# Beagle_ESC.net
KiCad netlist of a schematic drawn in EAGLE
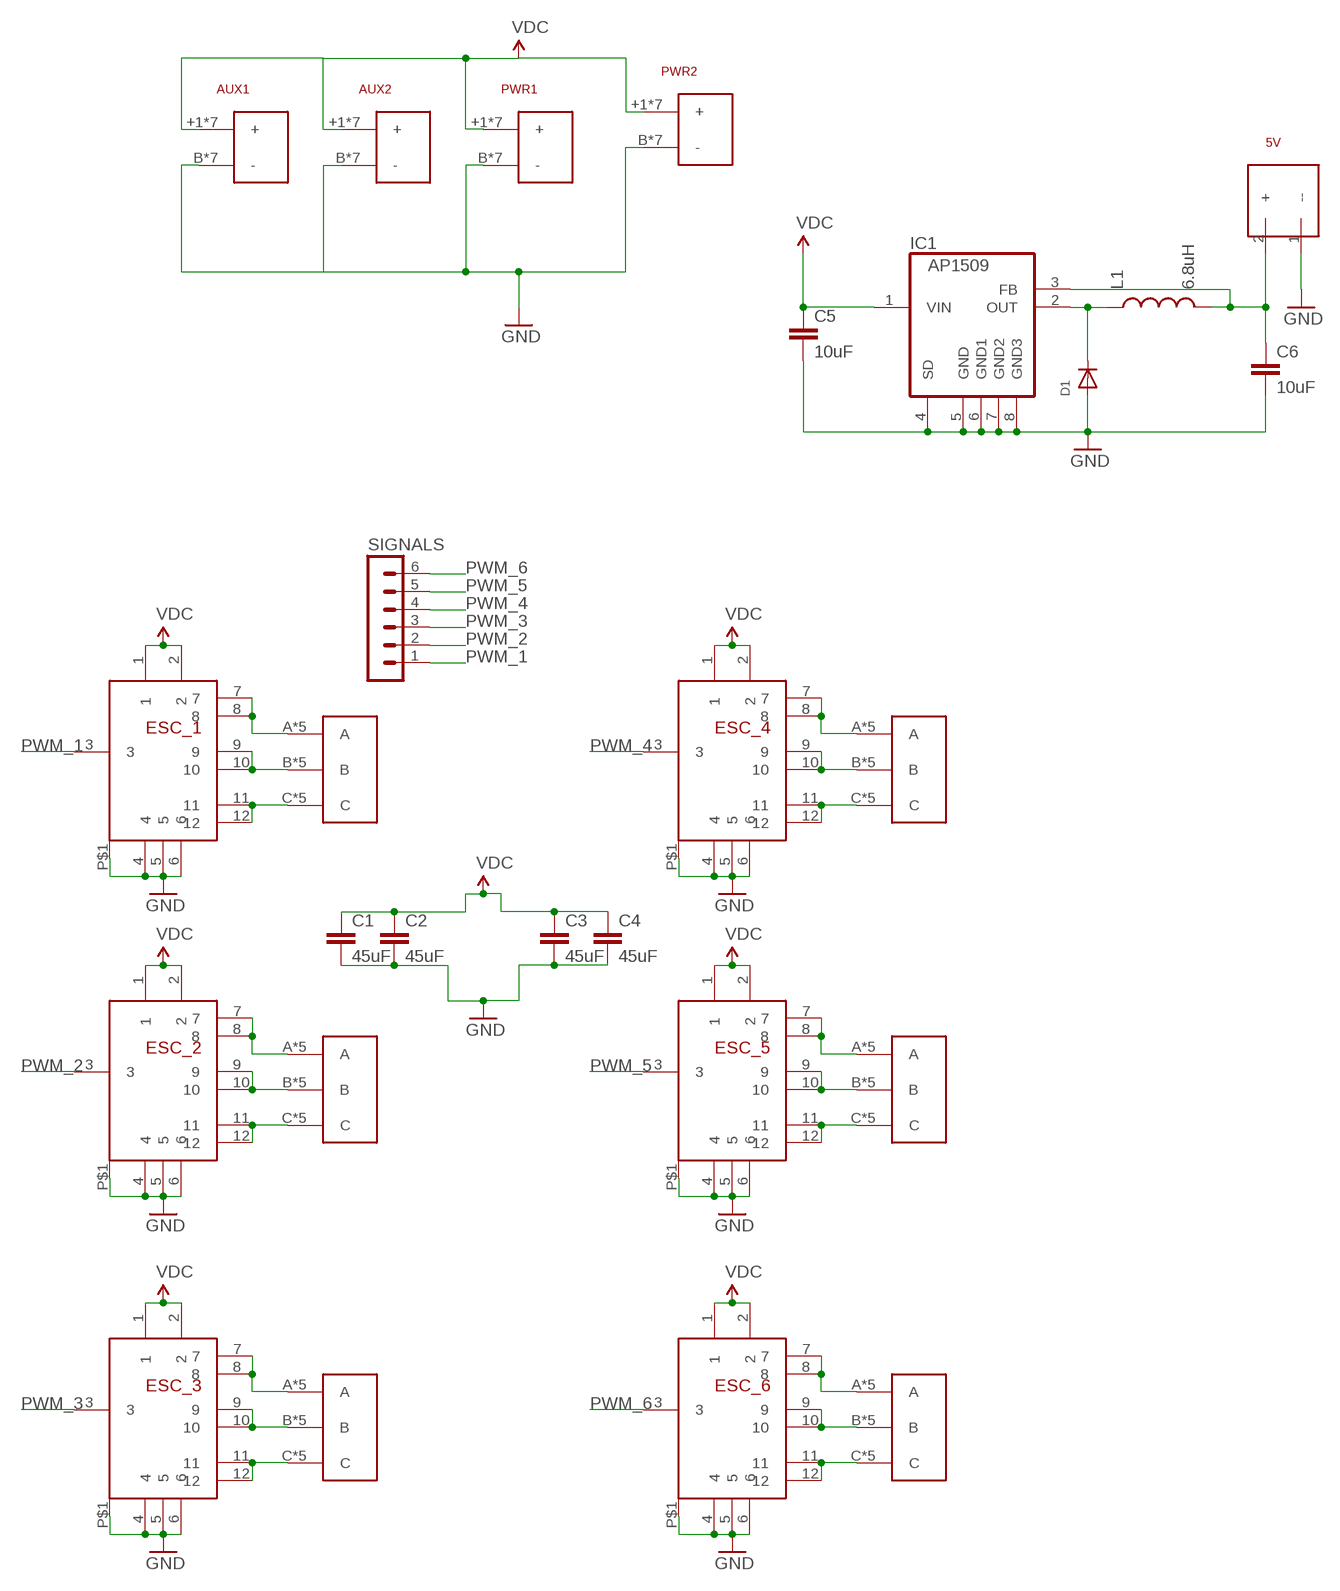
[diagram p0: schematic, sheet 1]

(export (version "E")
  (design (tool "Eeschema 10.0.6"))
  (components
    (comp (ref "1")
      (value "3_PADS")
      (footprint "eagle-import:3_PADS")
      (libsource (lib "eagle-import") (part "3_PADS"))
    )
    (comp (ref "2")
      (value "3_PADS")
      (footprint "eagle-import:3_PADS")
      (libsource (lib "eagle-import") (part "3_PADS"))
    )
    (comp (ref "3")
      (value "3_PADS")
      (footprint "eagle-import:3_PADS")
      (libsource (lib "eagle-import") (part "3_PADS"))
    )
    (comp (ref "4")
      (value "3_PADS")
      (footprint "eagle-import:3_PADS")
      (libsource (lib "eagle-import") (part "3_PADS"))
    )
    (comp (ref "5")
      (value "3_PADS")
      (footprint "eagle-import:3_PADS")
      (libsource (lib "eagle-import") (part "3_PADS"))
    )
    (comp (ref "5V")
      (value "HEADER_PWR")
      (footprint "eagle-import:HEADER_PWR")
      (libsource (lib "eagle-import") (part "HEADER_PWR"))
    )
    (comp (ref "6")
      (value "3_PADS")
      (footprint "eagle-import:3_PADS")
      (libsource (lib "eagle-import") (part "3_PADS"))
    )
    (comp (ref "AUX1")
      (value "2PADS")
      (footprint "eagle-import:2PADS")
      (libsource (lib "eagle-import") (part "2PADS"))
    )
    (comp (ref "AUX2")
      (value "2PADS")
      (footprint "eagle-import:2PADS")
      (libsource (lib "eagle-import") (part "2PADS"))
    )
    (comp (ref "C1")
      (value "45uF")
      (footprint "eagle-import:1206")
      (libsource (lib "eagle-import") (part "CAP1206"))
    )
    (comp (ref "C2")
      (value "45uF")
      (footprint "eagle-import:1206")
      (libsource (lib "eagle-import") (part "CAP1206"))
    )
    (comp (ref "C3")
      (value "45uF")
      (footprint "eagle-import:1206")
      (libsource (lib "eagle-import") (part "CAP1206"))
    )
    (comp (ref "C4")
      (value "45uF")
      (footprint "eagle-import:1206")
      (libsource (lib "eagle-import") (part "CAP1206"))
    )
    (comp (ref "C5")
      (value "10uF")
      (footprint "eagle-import:0805")
      (libsource (lib "eagle-import") (part "CAP0805"))
    )
    (comp (ref "C6")
      (value "10uF")
      (footprint "eagle-import:0805")
      (libsource (lib "eagle-import") (part "CAP0805"))
    )
    (comp (ref "D1")
      (value "DIODESOD-123")
      (footprint "eagle-import:SOD-123")
      (libsource (lib "eagle-import") (part "DIODESOD-123"))
    )
    (comp (ref "ESC_1")
      (value "DYS_BLHELI_ESC")
      (footprint "eagle-import:DYS_BLHELI_ESC")
      (libsource (lib "eagle-import") (part "DYS_BLHELI_ESC"))
    )
    (comp (ref "ESC_2")
      (value "DYS_BLHELI_ESC")
      (footprint "eagle-import:DYS_BLHELI_ESC")
      (libsource (lib "eagle-import") (part "DYS_BLHELI_ESC"))
    )
    (comp (ref "ESC_3")
      (value "DYS_BLHELI_ESC")
      (footprint "eagle-import:DYS_BLHELI_ESC")
      (libsource (lib "eagle-import") (part "DYS_BLHELI_ESC"))
    )
    (comp (ref "ESC_4")
      (value "DYS_BLHELI_ESC")
      (footprint "eagle-import:DYS_BLHELI_ESC")
      (libsource (lib "eagle-import") (part "DYS_BLHELI_ESC"))
    )
    (comp (ref "ESC_5")
      (value "DYS_BLHELI_ESC")
      (footprint "eagle-import:DYS_BLHELI_ESC")
      (libsource (lib "eagle-import") (part "DYS_BLHELI_ESC"))
    )
    (comp (ref "ESC_6")
      (value "DYS_BLHELI_ESC")
      (footprint "eagle-import:DYS_BLHELI_ESC")
      (libsource (lib "eagle-import") (part "DYS_BLHELI_ESC"))
    )
    (comp (ref "IC1")
      (value "AP1509SOIC-8-TIGHT")
      (footprint "eagle-import:SO08-TIGHT")
      (libsource (lib "eagle-import") (part "AP1509SOIC-8-TIGHT"))
    )
    (comp (ref "L1")
      (value "6.8uH")
      (footprint "eagle-import:TAIYO_NRS")
      (libsource (lib "eagle-import") (part "INDUCTORTAIYO_NR-S"))
    )
    (comp (ref "PWR1")
      (value "2PADS")
      (footprint "eagle-import:2PADS")
      (libsource (lib "eagle-import") (part "2PADS"))
    )
    (comp (ref "PWR2")
      (value "2PADS")
      (footprint "eagle-import:2PADS")
      (libsource (lib "eagle-import") (part "2PADS"))
    )
    (comp (ref "SIGNALS")
      (value "MA06-1")
      (footprint "eagle-import:MA06-1")
      (libsource (lib "eagle-import") (part "MA06-1"))
    )
  )
  (nets
    (net (code "1") (name "/PWM_1") (class "Default")
      (node (ref "ESC_1") (pin "3") (pinfunction "3_3") (pintype "input"))
      (node (ref "SIGNALS") (pin "1") (pinfunction "1_1") (pintype "passive"))
    )
    (net (code "2") (name "/PWM_2") (class "Default")
      (node (ref "ESC_2") (pin "3") (pinfunction "3_3") (pintype "input"))
      (node (ref "SIGNALS") (pin "2") (pinfunction "2_2") (pintype "passive"))
    )
    (net (code "3") (name "/PWM_3") (class "Default")
      (node (ref "ESC_3") (pin "3") (pinfunction "3_3") (pintype "input"))
      (node (ref "SIGNALS") (pin "3") (pinfunction "3_3") (pintype "passive"))
    )
    (net (code "4") (name "/PWM_4") (class "Default")
      (node (ref "ESC_4") (pin "3") (pinfunction "3_3") (pintype "input"))
      (node (ref "SIGNALS") (pin "4") (pinfunction "4_4") (pintype "passive"))
    )
    (net (code "5") (name "/PWM_5") (class "Default")
      (node (ref "ESC_5") (pin "3") (pinfunction "3_3") (pintype "input"))
      (node (ref "SIGNALS") (pin "5") (pinfunction "5_5") (pintype "passive"))
    )
    (net (code "6") (name "/PWM_6") (class "Default")
      (node (ref "ESC_6") (pin "3") (pinfunction "3_3") (pintype "input"))
      (node (ref "SIGNALS") (pin "6") (pinfunction "6_6") (pintype "passive"))
    )
    (net (code "7") (name "GND") (class "Default")
      (node (ref "5V") (pin "1") (pinfunction "--_1") (pintype "bidirectional"))
      (node (ref "AUX1") (pin "B") (pinfunction "-_B") (pintype "bidirectional"))
      (node (ref "AUX1") (pin "P$10") (pinfunction "-_P$10") (pintype "bidirectional"))
      (node (ref "AUX1") (pin "P$11") (pinfunction "-_P$11") (pintype "bidirectional"))
      (node (ref "AUX1") (pin "P$12") (pinfunction "-_P$12") (pintype "bidirectional"))
      (node (ref "AUX1") (pin "P$13") (pinfunction "-_P$13") (pintype "bidirectional"))
      (node (ref "AUX1") (pin "P$14") (pinfunction "-_P$14") (pintype "bidirectional"))
      (node (ref "AUX1") (pin "P$5") (pinfunction "-_P$5") (pintype "bidirectional"))
      (node (ref "AUX2") (pin "B") (pinfunction "-_B") (pintype "bidirectional"))
      (node (ref "AUX2") (pin "P$10") (pinfunction "-_P$10") (pintype "bidirectional"))
      (node (ref "AUX2") (pin "P$11") (pinfunction "-_P$11") (pintype "bidirectional"))
      (node (ref "AUX2") (pin "P$12") (pinfunction "-_P$12") (pintype "bidirectional"))
      (node (ref "AUX2") (pin "P$13") (pinfunction "-_P$13") (pintype "bidirectional"))
      (node (ref "AUX2") (pin "P$14") (pinfunction "-_P$14") (pintype "bidirectional"))
      (node (ref "AUX2") (pin "P$5") (pinfunction "-_P$5") (pintype "bidirectional"))
      (node (ref "C1") (pin "2") (pinfunction "2_2") (pintype "passive"))
      (node (ref "C2") (pin "2") (pinfunction "2_2") (pintype "passive"))
      (node (ref "C3") (pin "2") (pinfunction "2_2") (pintype "passive"))
      (node (ref "C4") (pin "2") (pinfunction "2_2") (pintype "passive"))
      (node (ref "C5") (pin "2") (pinfunction "2_2") (pintype "passive"))
      (node (ref "C6") (pin "2") (pinfunction "2_2") (pintype "passive"))
      (node (ref "D1") (pin "A") (pinfunction "A_A") (pintype "passive"))
      (node (ref "ESC_1") (pin "4") (pinfunction "4_4") (pintype "power_in"))
      (node (ref "ESC_1") (pin "5") (pinfunction "5_5") (pintype "power_in"))
      (node (ref "ESC_1") (pin "6") (pinfunction "6_6") (pintype "power_in"))
      (node (ref "ESC_1") (pin "P$1") (pinfunction "P$1_P$1") (pintype "power_in"))
      (node (ref "ESC_2") (pin "4") (pinfunction "4_4") (pintype "power_in"))
      (node (ref "ESC_2") (pin "5") (pinfunction "5_5") (pintype "power_in"))
      (node (ref "ESC_2") (pin "6") (pinfunction "6_6") (pintype "power_in"))
      (node (ref "ESC_2") (pin "P$1") (pinfunction "P$1_P$1") (pintype "power_in"))
      (node (ref "ESC_3") (pin "4") (pinfunction "4_4") (pintype "power_in"))
      (node (ref "ESC_3") (pin "5") (pinfunction "5_5") (pintype "power_in"))
      (node (ref "ESC_3") (pin "6") (pinfunction "6_6") (pintype "power_in"))
      (node (ref "ESC_3") (pin "P$1") (pinfunction "P$1_P$1") (pintype "power_in"))
      (node (ref "ESC_4") (pin "4") (pinfunction "4_4") (pintype "power_in"))
      (node (ref "ESC_4") (pin "5") (pinfunction "5_5") (pintype "power_in"))
      (node (ref "ESC_4") (pin "6") (pinfunction "6_6") (pintype "power_in"))
      (node (ref "ESC_4") (pin "P$1") (pinfunction "P$1_P$1") (pintype "power_in"))
      (node (ref "ESC_5") (pin "4") (pinfunction "4_4") (pintype "power_in"))
      (node (ref "ESC_5") (pin "5") (pinfunction "5_5") (pintype "power_in"))
      (node (ref "ESC_5") (pin "6") (pinfunction "6_6") (pintype "power_in"))
      (node (ref "ESC_5") (pin "P$1") (pinfunction "P$1_P$1") (pintype "power_in"))
      (node (ref "ESC_6") (pin "4") (pinfunction "4_4") (pintype "power_in"))
      (node (ref "ESC_6") (pin "5") (pinfunction "5_5") (pintype "power_in"))
      (node (ref "ESC_6") (pin "6") (pinfunction "6_6") (pintype "power_in"))
      (node (ref "ESC_6") (pin "P$1") (pinfunction "P$1_P$1") (pintype "power_in"))
      (node (ref "IC1") (pin "4") (pinfunction "SD_4") (pintype "input"))
      (node (ref "IC1") (pin "5") (pinfunction "GND_5") (pintype "power_in"))
      (node (ref "IC1") (pin "6") (pinfunction "GND1_6") (pintype "input"))
      (node (ref "IC1") (pin "7") (pinfunction "GND2_7") (pintype "passive"))
      (node (ref "IC1") (pin "8") (pinfunction "GND3_8") (pintype "power_in"))
      (node (ref "PWR1") (pin "B") (pinfunction "-_B") (pintype "bidirectional"))
      (node (ref "PWR1") (pin "P$10") (pinfunction "-_P$10") (pintype "bidirectional"))
      (node (ref "PWR1") (pin "P$11") (pinfunction "-_P$11") (pintype "bidirectional"))
      (node (ref "PWR1") (pin "P$12") (pinfunction "-_P$12") (pintype "bidirectional"))
      (node (ref "PWR1") (pin "P$13") (pinfunction "-_P$13") (pintype "bidirectional"))
      (node (ref "PWR1") (pin "P$14") (pinfunction "-_P$14") (pintype "bidirectional"))
      (node (ref "PWR1") (pin "P$5") (pinfunction "-_P$5") (pintype "bidirectional"))
      (node (ref "PWR2") (pin "B") (pinfunction "-_B") (pintype "bidirectional"))
      (node (ref "PWR2") (pin "P$10") (pinfunction "-_P$10") (pintype "bidirectional"))
      (node (ref "PWR2") (pin "P$11") (pinfunction "-_P$11") (pintype "bidirectional"))
      (node (ref "PWR2") (pin "P$12") (pinfunction "-_P$12") (pintype "bidirectional"))
      (node (ref "PWR2") (pin "P$13") (pinfunction "-_P$13") (pintype "bidirectional"))
      (node (ref "PWR2") (pin "P$14") (pinfunction "-_P$14") (pintype "bidirectional"))
      (node (ref "PWR2") (pin "P$5") (pinfunction "-_P$5") (pintype "bidirectional"))
    )
    (net (code "8") (name "Net-(1-A-PadP$4)") (class "Default")
      (node (ref "1") (pin "A") (pinfunction "A_A") (pintype "bidirectional"))
      (node (ref "1") (pin "P$4") (pinfunction "A_P$4") (pintype "bidirectional"))
      (node (ref "1") (pin "P$7") (pinfunction "A_P$7") (pintype "bidirectional"))
      (node (ref "1") (pin "P$8") (pinfunction "A_P$8") (pintype "bidirectional"))
      (node (ref "1") (pin "P$9") (pinfunction "A_P$9") (pintype "bidirectional"))
      (node (ref "ESC_1") (pin "7") (pinfunction "7_7") (pintype "output"))
      (node (ref "ESC_1") (pin "8") (pinfunction "8_8") (pintype "output"))
    )
    (net (code "9") (name "Net-(1-B-PadP$10)") (class "Default")
      (node (ref "1") (pin "B") (pinfunction "B_B") (pintype "bidirectional"))
      (node (ref "1") (pin "P$10") (pinfunction "B_P$10") (pintype "bidirectional"))
      (node (ref "1") (pin "P$11") (pinfunction "B_P$11") (pintype "bidirectional"))
      (node (ref "1") (pin "P$12") (pinfunction "B_P$12") (pintype "bidirectional"))
      (node (ref "1") (pin "P$5") (pinfunction "B_P$5") (pintype "bidirectional"))
      (node (ref "ESC_1") (pin "10") (pinfunction "10_10") (pintype "output"))
      (node (ref "ESC_1") (pin "9") (pinfunction "9_9") (pintype "output"))
    )
    (net (code "10") (name "Net-(1-C-PadP$13)") (class "Default")
      (node (ref "1") (pin "C") (pinfunction "C_C") (pintype "bidirectional"))
      (node (ref "1") (pin "P$13") (pinfunction "C_P$13") (pintype "bidirectional"))
      (node (ref "1") (pin "P$14") (pinfunction "C_P$14") (pintype "bidirectional"))
      (node (ref "1") (pin "P$15") (pinfunction "C_P$15") (pintype "bidirectional"))
      (node (ref "1") (pin "P$6") (pinfunction "C_P$6") (pintype "bidirectional"))
      (node (ref "ESC_1") (pin "11") (pinfunction "11_11") (pintype "output"))
      (node (ref "ESC_1") (pin "12") (pinfunction "12_12") (pintype "output"))
    )
    (net (code "11") (name "Net-(2-A-PadP$4)") (class "Default")
      (node (ref "2") (pin "A") (pinfunction "A_A") (pintype "bidirectional"))
      (node (ref "2") (pin "P$4") (pinfunction "A_P$4") (pintype "bidirectional"))
      (node (ref "2") (pin "P$7") (pinfunction "A_P$7") (pintype "bidirectional"))
      (node (ref "2") (pin "P$8") (pinfunction "A_P$8") (pintype "bidirectional"))
      (node (ref "2") (pin "P$9") (pinfunction "A_P$9") (pintype "bidirectional"))
      (node (ref "ESC_2") (pin "7") (pinfunction "7_7") (pintype "output"))
      (node (ref "ESC_2") (pin "8") (pinfunction "8_8") (pintype "output"))
    )
    (net (code "12") (name "Net-(2-B-PadP$10)") (class "Default")
      (node (ref "2") (pin "B") (pinfunction "B_B") (pintype "bidirectional"))
      (node (ref "2") (pin "P$10") (pinfunction "B_P$10") (pintype "bidirectional"))
      (node (ref "2") (pin "P$11") (pinfunction "B_P$11") (pintype "bidirectional"))
      (node (ref "2") (pin "P$12") (pinfunction "B_P$12") (pintype "bidirectional"))
      (node (ref "2") (pin "P$5") (pinfunction "B_P$5") (pintype "bidirectional"))
      (node (ref "ESC_2") (pin "10") (pinfunction "10_10") (pintype "output"))
      (node (ref "ESC_2") (pin "9") (pinfunction "9_9") (pintype "output"))
    )
    (net (code "13") (name "Net-(2-C-PadP$13)") (class "Default")
      (node (ref "2") (pin "C") (pinfunction "C_C") (pintype "bidirectional"))
      (node (ref "2") (pin "P$13") (pinfunction "C_P$13") (pintype "bidirectional"))
      (node (ref "2") (pin "P$14") (pinfunction "C_P$14") (pintype "bidirectional"))
      (node (ref "2") (pin "P$15") (pinfunction "C_P$15") (pintype "bidirectional"))
      (node (ref "2") (pin "P$6") (pinfunction "C_P$6") (pintype "bidirectional"))
      (node (ref "ESC_2") (pin "11") (pinfunction "11_11") (pintype "output"))
      (node (ref "ESC_2") (pin "12") (pinfunction "12_12") (pintype "output"))
    )
    (net (code "14") (name "Net-(3-A-PadP$4)") (class "Default")
      (node (ref "3") (pin "A") (pinfunction "A_A") (pintype "bidirectional"))
      (node (ref "3") (pin "P$4") (pinfunction "A_P$4") (pintype "bidirectional"))
      (node (ref "3") (pin "P$7") (pinfunction "A_P$7") (pintype "bidirectional"))
      (node (ref "3") (pin "P$8") (pinfunction "A_P$8") (pintype "bidirectional"))
      (node (ref "3") (pin "P$9") (pinfunction "A_P$9") (pintype "bidirectional"))
      (node (ref "ESC_3") (pin "7") (pinfunction "7_7") (pintype "output"))
      (node (ref "ESC_3") (pin "8") (pinfunction "8_8") (pintype "output"))
    )
    (net (code "15") (name "Net-(3-B-PadP$10)") (class "Default")
      (node (ref "3") (pin "B") (pinfunction "B_B") (pintype "bidirectional"))
      (node (ref "3") (pin "P$10") (pinfunction "B_P$10") (pintype "bidirectional"))
      (node (ref "3") (pin "P$11") (pinfunction "B_P$11") (pintype "bidirectional"))
      (node (ref "3") (pin "P$12") (pinfunction "B_P$12") (pintype "bidirectional"))
      (node (ref "3") (pin "P$5") (pinfunction "B_P$5") (pintype "bidirectional"))
      (node (ref "ESC_3") (pin "10") (pinfunction "10_10") (pintype "output"))
      (node (ref "ESC_3") (pin "9") (pinfunction "9_9") (pintype "output"))
    )
    (net (code "16") (name "Net-(3-C-PadP$13)") (class "Default")
      (node (ref "3") (pin "C") (pinfunction "C_C") (pintype "bidirectional"))
      (node (ref "3") (pin "P$13") (pinfunction "C_P$13") (pintype "bidirectional"))
      (node (ref "3") (pin "P$14") (pinfunction "C_P$14") (pintype "bidirectional"))
      (node (ref "3") (pin "P$15") (pinfunction "C_P$15") (pintype "bidirectional"))
      (node (ref "3") (pin "P$6") (pinfunction "C_P$6") (pintype "bidirectional"))
      (node (ref "ESC_3") (pin "11") (pinfunction "11_11") (pintype "output"))
      (node (ref "ESC_3") (pin "12") (pinfunction "12_12") (pintype "output"))
    )
    (net (code "17") (name "Net-(4-A-PadP$4)") (class "Default")
      (node (ref "4") (pin "A") (pinfunction "A_A") (pintype "bidirectional"))
      (node (ref "4") (pin "P$4") (pinfunction "A_P$4") (pintype "bidirectional"))
      (node (ref "4") (pin "P$7") (pinfunction "A_P$7") (pintype "bidirectional"))
      (node (ref "4") (pin "P$8") (pinfunction "A_P$8") (pintype "bidirectional"))
      (node (ref "4") (pin "P$9") (pinfunction "A_P$9") (pintype "bidirectional"))
      (node (ref "ESC_4") (pin "7") (pinfunction "7_7") (pintype "output"))
      (node (ref "ESC_4") (pin "8") (pinfunction "8_8") (pintype "output"))
    )
    (net (code "18") (name "Net-(4-B-PadP$10)") (class "Default")
      (node (ref "4") (pin "B") (pinfunction "B_B") (pintype "bidirectional"))
      (node (ref "4") (pin "P$10") (pinfunction "B_P$10") (pintype "bidirectional"))
      (node (ref "4") (pin "P$11") (pinfunction "B_P$11") (pintype "bidirectional"))
      (node (ref "4") (pin "P$12") (pinfunction "B_P$12") (pintype "bidirectional"))
      (node (ref "4") (pin "P$5") (pinfunction "B_P$5") (pintype "bidirectional"))
      (node (ref "ESC_4") (pin "10") (pinfunction "10_10") (pintype "output"))
      (node (ref "ESC_4") (pin "9") (pinfunction "9_9") (pintype "output"))
    )
    (net (code "19") (name "Net-(4-C-PadP$13)") (class "Default")
      (node (ref "4") (pin "C") (pinfunction "C_C") (pintype "bidirectional"))
      (node (ref "4") (pin "P$13") (pinfunction "C_P$13") (pintype "bidirectional"))
      (node (ref "4") (pin "P$14") (pinfunction "C_P$14") (pintype "bidirectional"))
      (node (ref "4") (pin "P$15") (pinfunction "C_P$15") (pintype "bidirectional"))
      (node (ref "4") (pin "P$6") (pinfunction "C_P$6") (pintype "bidirectional"))
      (node (ref "ESC_4") (pin "11") (pinfunction "11_11") (pintype "output"))
      (node (ref "ESC_4") (pin "12") (pinfunction "12_12") (pintype "output"))
    )
    (net (code "20") (name "Net-(5-A-PadP$4)") (class "Default")
      (node (ref "5") (pin "A") (pinfunction "A_A") (pintype "bidirectional"))
      (node (ref "5") (pin "P$4") (pinfunction "A_P$4") (pintype "bidirectional"))
      (node (ref "5") (pin "P$7") (pinfunction "A_P$7") (pintype "bidirectional"))
      (node (ref "5") (pin "P$8") (pinfunction "A_P$8") (pintype "bidirectional"))
      (node (ref "5") (pin "P$9") (pinfunction "A_P$9") (pintype "bidirectional"))
      (node (ref "ESC_5") (pin "7") (pinfunction "7_7") (pintype "output"))
      (node (ref "ESC_5") (pin "8") (pinfunction "8_8") (pintype "output"))
    )
    (net (code "21") (name "Net-(5-B-PadP$10)") (class "Default")
      (node (ref "5") (pin "B") (pinfunction "B_B") (pintype "bidirectional"))
      (node (ref "5") (pin "P$10") (pinfunction "B_P$10") (pintype "bidirectional"))
      (node (ref "5") (pin "P$11") (pinfunction "B_P$11") (pintype "bidirectional"))
      (node (ref "5") (pin "P$12") (pinfunction "B_P$12") (pintype "bidirectional"))
      (node (ref "5") (pin "P$5") (pinfunction "B_P$5") (pintype "bidirectional"))
      (node (ref "ESC_5") (pin "10") (pinfunction "10_10") (pintype "output"))
      (node (ref "ESC_5") (pin "9") (pinfunction "9_9") (pintype "output"))
    )
    (net (code "22") (name "Net-(5-C-PadP$13)") (class "Default")
      (node (ref "5") (pin "C") (pinfunction "C_C") (pintype "bidirectional"))
      (node (ref "5") (pin "P$13") (pinfunction "C_P$13") (pintype "bidirectional"))
      (node (ref "5") (pin "P$14") (pinfunction "C_P$14") (pintype "bidirectional"))
      (node (ref "5") (pin "P$15") (pinfunction "C_P$15") (pintype "bidirectional"))
      (node (ref "5") (pin "P$6") (pinfunction "C_P$6") (pintype "bidirectional"))
      (node (ref "ESC_5") (pin "11") (pinfunction "11_11") (pintype "output"))
      (node (ref "ESC_5") (pin "12") (pinfunction "12_12") (pintype "output"))
    )
    (net (code "23") (name "Net-(5V-+)") (class "Default")
      (node (ref "5V") (pin "2") (pinfunction "+_2") (pintype "bidirectional"))
      (node (ref "C6") (pin "1") (pinfunction "1_1") (pintype "passive"))
      (node (ref "IC1") (pin "3") (pinfunction "FB_3") (pintype "output"))
      (node (ref "L1") (pin "2") (pinfunction "2_2") (pintype "passive"))
    )
    (net (code "24") (name "Net-(6-A-PadP$4)") (class "Default")
      (node (ref "6") (pin "A") (pinfunction "A_A") (pintype "bidirectional"))
      (node (ref "6") (pin "P$4") (pinfunction "A_P$4") (pintype "bidirectional"))
      (node (ref "6") (pin "P$7") (pinfunction "A_P$7") (pintype "bidirectional"))
      (node (ref "6") (pin "P$8") (pinfunction "A_P$8") (pintype "bidirectional"))
      (node (ref "6") (pin "P$9") (pinfunction "A_P$9") (pintype "bidirectional"))
      (node (ref "ESC_6") (pin "7") (pinfunction "7_7") (pintype "output"))
      (node (ref "ESC_6") (pin "8") (pinfunction "8_8") (pintype "output"))
    )
    (net (code "25") (name "Net-(6-B-PadP$10)") (class "Default")
      (node (ref "6") (pin "B") (pinfunction "B_B") (pintype "bidirectional"))
      (node (ref "6") (pin "P$10") (pinfunction "B_P$10") (pintype "bidirectional"))
      (node (ref "6") (pin "P$11") (pinfunction "B_P$11") (pintype "bidirectional"))
      (node (ref "6") (pin "P$12") (pinfunction "B_P$12") (pintype "bidirectional"))
      (node (ref "6") (pin "P$5") (pinfunction "B_P$5") (pintype "bidirectional"))
      (node (ref "ESC_6") (pin "10") (pinfunction "10_10") (pintype "output"))
      (node (ref "ESC_6") (pin "9") (pinfunction "9_9") (pintype "output"))
    )
    (net (code "26") (name "Net-(6-C-PadP$13)") (class "Default")
      (node (ref "6") (pin "C") (pinfunction "C_C") (pintype "bidirectional"))
      (node (ref "6") (pin "P$13") (pinfunction "C_P$13") (pintype "bidirectional"))
      (node (ref "6") (pin "P$14") (pinfunction "C_P$14") (pintype "bidirectional"))
      (node (ref "6") (pin "P$15") (pinfunction "C_P$15") (pintype "bidirectional"))
      (node (ref "6") (pin "P$6") (pinfunction "C_P$6") (pintype "bidirectional"))
      (node (ref "ESC_6") (pin "11") (pinfunction "11_11") (pintype "output"))
      (node (ref "ESC_6") (pin "12") (pinfunction "12_12") (pintype "output"))
    )
    (net (code "27") (name "Net-(IC1-OUT)") (class "Default")
      (node (ref "D1") (pin "C") (pinfunction "C_C") (pintype "passive"))
      (node (ref "IC1") (pin "2") (pinfunction "OUT_2") (pintype "output"))
      (node (ref "L1") (pin "1") (pinfunction "1_1") (pintype "passive"))
    )
    (net (code "28") (name "VDC") (class "Default")
      (node (ref "AUX1") (pin "+1") (pinfunction "+_+1") (pintype "bidirectional"))
      (node (ref "AUX1") (pin "+2") (pinfunction "+_+2") (pintype "bidirectional"))
      (node (ref "AUX1") (pin "+3") (pinfunction "+_+3") (pintype "bidirectional"))
      (node (ref "AUX1") (pin "+4") (pinfunction "+_+4") (pintype "bidirectional"))
      (node (ref "AUX1") (pin "+5") (pinfunction "+_+5") (pintype "bidirectional"))
      (node (ref "AUX1") (pin "+BOTTOM") (pinfunction "+_+BOTTOM") (pintype "bidirectional"))
      (node (ref "AUX1") (pin "+TOP") (pinfunction "+_+TOP") (pintype "bidirectional"))
      (node (ref "AUX2") (pin "+1") (pinfunction "+_+1") (pintype "bidirectional"))
      (node (ref "AUX2") (pin "+2") (pinfunction "+_+2") (pintype "bidirectional"))
      (node (ref "AUX2") (pin "+3") (pinfunction "+_+3") (pintype "bidirectional"))
      (node (ref "AUX2") (pin "+4") (pinfunction "+_+4") (pintype "bidirectional"))
      (node (ref "AUX2") (pin "+5") (pinfunction "+_+5") (pintype "bidirectional"))
      (node (ref "AUX2") (pin "+BOTTOM") (pinfunction "+_+BOTTOM") (pintype "bidirectional"))
      (node (ref "AUX2") (pin "+TOP") (pinfunction "+_+TOP") (pintype "bidirectional"))
      (node (ref "C1") (pin "1") (pinfunction "1_1") (pintype "passive"))
      (node (ref "C2") (pin "1") (pinfunction "1_1") (pintype "passive"))
      (node (ref "C3") (pin "1") (pinfunction "1_1") (pintype "passive"))
      (node (ref "C4") (pin "1") (pinfunction "1_1") (pintype "passive"))
      (node (ref "C5") (pin "1") (pinfunction "1_1") (pintype "passive"))
      (node (ref "ESC_1") (pin "1") (pinfunction "1_1") (pintype "power_in"))
      (node (ref "ESC_1") (pin "2") (pinfunction "2_2") (pintype "power_in"))
      (node (ref "ESC_2") (pin "1") (pinfunction "1_1") (pintype "power_in"))
      (node (ref "ESC_2") (pin "2") (pinfunction "2_2") (pintype "power_in"))
      (node (ref "ESC_3") (pin "1") (pinfunction "1_1") (pintype "power_in"))
      (node (ref "ESC_3") (pin "2") (pinfunction "2_2") (pintype "power_in"))
      (node (ref "ESC_4") (pin "1") (pinfunction "1_1") (pintype "power_in"))
      (node (ref "ESC_4") (pin "2") (pinfunction "2_2") (pintype "power_in"))
      (node (ref "ESC_5") (pin "1") (pinfunction "1_1") (pintype "power_in"))
      (node (ref "ESC_5") (pin "2") (pinfunction "2_2") (pintype "power_in"))
      (node (ref "ESC_6") (pin "1") (pinfunction "1_1") (pintype "power_in"))
      (node (ref "ESC_6") (pin "2") (pinfunction "2_2") (pintype "power_in"))
      (node (ref "IC1") (pin "1") (pinfunction "VIN_1") (pintype "input"))
      (node (ref "PWR1") (pin "+1") (pinfunction "+_+1") (pintype "bidirectional"))
      (node (ref "PWR1") (pin "+2") (pinfunction "+_+2") (pintype "bidirectional"))
      (node (ref "PWR1") (pin "+3") (pinfunction "+_+3") (pintype "bidirectional"))
      (node (ref "PWR1") (pin "+4") (pinfunction "+_+4") (pintype "bidirectional"))
      (node (ref "PWR1") (pin "+5") (pinfunction "+_+5") (pintype "bidirectional"))
      (node (ref "PWR1") (pin "+BOTTOM") (pinfunction "+_+BOTTOM") (pintype "bidirectional"))
      (node (ref "PWR1") (pin "+TOP") (pinfunction "+_+TOP") (pintype "bidirectional"))
      (node (ref "PWR2") (pin "+1") (pinfunction "+_+1") (pintype "bidirectional"))
      (node (ref "PWR2") (pin "+2") (pinfunction "+_+2") (pintype "bidirectional"))
      (node (ref "PWR2") (pin "+3") (pinfunction "+_+3") (pintype "bidirectional"))
      (node (ref "PWR2") (pin "+4") (pinfunction "+_+4") (pintype "bidirectional"))
      (node (ref "PWR2") (pin "+5") (pinfunction "+_+5") (pintype "bidirectional"))
      (node (ref "PWR2") (pin "+BOTTOM") (pinfunction "+_+BOTTOM") (pintype "bidirectional"))
      (node (ref "PWR2") (pin "+TOP") (pinfunction "+_+TOP") (pintype "bidirectional"))
    )
  )
)
